# External_boards.net
KiCad netlist of a schematic drawn in Altium Designer
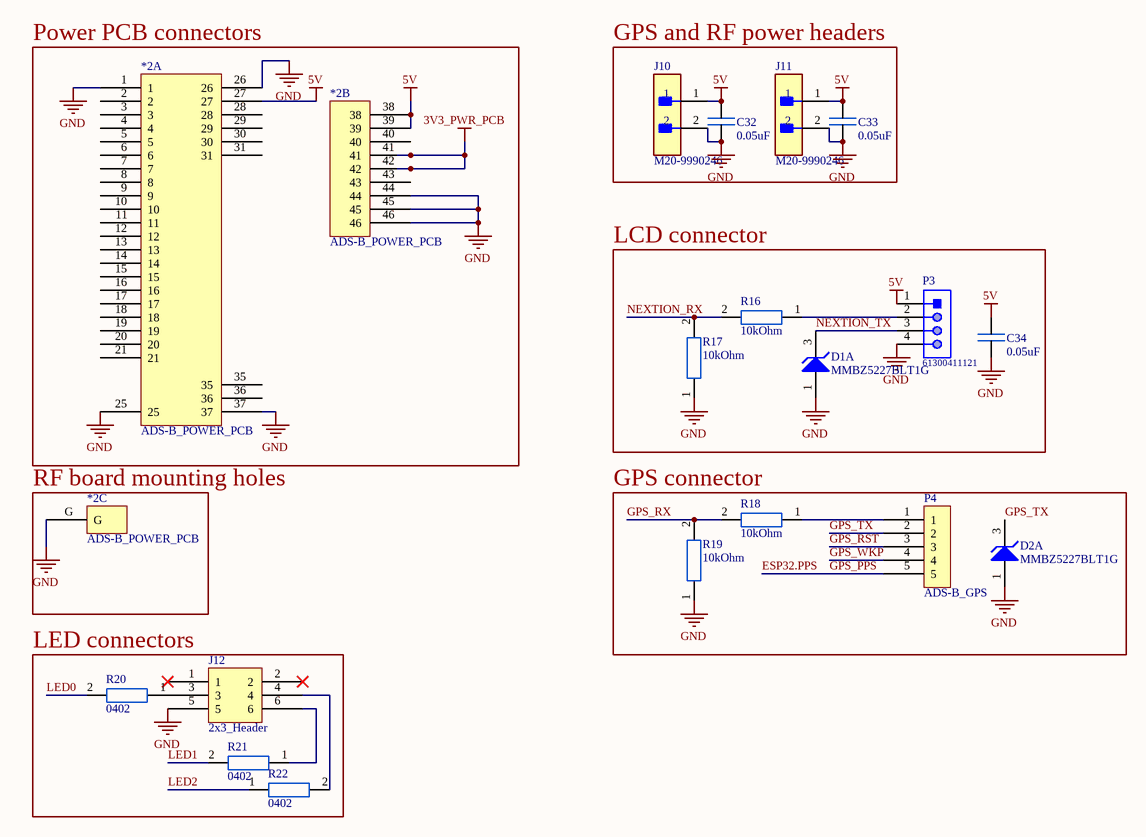
[diagram p0: External_boards.SchDoc]

(export (version "E")
  (design (tool "Eeschema 10.0.6"))
  (components
    (comp (ref "*2")
      (value "ADS-B_POWER_PCB")
      (footprint "ADS-B_POWER_PCB")
      (libsource (lib "Schlib1") (part "ADS-B_POWER_PCB"))
    )
    (comp (ref "C32")
      (value "0.05uF")
      (footprint "0402_footprint")
      (description "0402 capacitor")
      (libsource (lib "Schlib1") (part "Capacitor_0402"))
    )
    (comp (ref "C33")
      (value "0.05uF")
      (footprint "0402_footprint")
      (description "0402 capacitor")
      (libsource (lib "Schlib1") (part "Capacitor_0402"))
    )
    (comp (ref "C34")
      (value "0.05uF")
      (footprint "0402_footprint")
      (description "0402 capacitor")
      (libsource (lib "Schlib1") (part "Capacitor_0402"))
    )
    (comp (ref "D1")
      (value "MMBZ5227BLT1G")
      (footprint "ONSC-SOT-23-3-318-08_V")
      (description "Zener Voltage Regulator, 225 mW, 3-Pin SOT-23, Pb-Free, Tape and Reel")
      (fields (field (name "MANUFACTURER") "On Semiconductor"))
      (libsource (lib "Altium Content Vault") (part "ONSC-A1K3-3"))
    )
    (comp (ref "D2")
      (value "MMBZ5227BLT1G")
      (footprint "ONSC-SOT-23-3-318-08_V")
      (description "Zener Voltage Regulator, 225 mW, 3-Pin SOT-23, Pb-Free, Tape and Reel")
      (fields (field (name "MANUFACTURER") "On Semiconductor"))
      (libsource (lib "Altium Content Vault") (part "ONSC-A1K3-3"))
    )
    (comp (ref "J10")
      (value "M20-9990246")
      (footprint "FP-M20-9990246-MFG")
      (description "CONN HEADER VERT 2POS 2.54MM")
      (fields
        (field (name "OCTOPART") "https://octopart.com/m20-9990246-harwin-2590635")
        (field (name "MANUFACTURER") "Harwin")
      )
      (libsource (lib "Altium Content Vault") (part "3bc925449376181038e59eaffc5286c"))
    )
    (comp (ref "J11")
      (value "M20-9990246")
      (footprint "FP-M20-9990246-MFG")
      (description "CONN HEADER VERT 2POS 2.54MM")
      (fields
        (field (name "OCTOPART") "https://octopart.com/m20-9990246-harwin-2590635")
        (field (name "MANUFACTURER") "Harwin")
      )
      (libsource (lib "Altium Content Vault") (part "3bc925449376181038e59eaffc5286c"))
    )
    (comp (ref "J12")
      (value "2x3_Header")
      (footprint "2x3 header")
      (libsource (lib "Schlib1") (part "2x3_Header"))
    )
    (comp (ref "P3")
      (value "61300411121")
      (footprint "61300411121")
      (description "THT Vertical Pin Header WR-PHD, Pitch 2.54 mm, Single Row, 4 pins")
      (fields (field (name "MANUFACTURER") "Wurth Elektronik") (field (name "PUBLISHER") "WurthElektronik"))
      (libsource (lib "Altium Content Vault") (part "WE-CN-1P-M-R4"))
    )
    (comp (ref "P4")
      (value "ADS-B_GPS")
      (footprint "ADS-B_GPS")
      (libsource (lib "Schlib1") (part "ADS-B_GPS"))
    )
    (comp (ref "R16")
      (value "10kOhm")
      (footprint "0402_footprint")
      (description "0402 resistor")
      (libsource (lib "Schlib1") (part "Resistor_0402"))
    )
    (comp (ref "R17")
      (value "10kOhm")
      (footprint "0402_footprint")
      (description "0402 resistor")
      (libsource (lib "Schlib1") (part "Resistor_0402"))
    )
    (comp (ref "R18")
      (value "10kOhm")
      (footprint "0402_footprint")
      (description "0402 resistor")
      (libsource (lib "Schlib1") (part "Resistor_0402"))
    )
    (comp (ref "R19")
      (value "10kOhm")
      (footprint "0402_footprint")
      (description "0402 resistor")
      (libsource (lib "Schlib1") (part "Resistor_0402"))
    )
    (comp (ref "R20")
      (value "0402")
      (footprint "0402_footprint")
      (description "0402 resistor")
      (libsource (lib "Schlib1") (part "Resistor_0402"))
    )
    (comp (ref "R21")
      (value "0402")
      (footprint "0402_footprint")
      (description "0402 resistor")
      (libsource (lib "Schlib1") (part "Resistor_0402"))
    )
    (comp (ref "R22")
      (value "0402")
      (footprint "0402_footprint")
      (description "0402 resistor")
      (libsource (lib "Schlib1") (part "Resistor_0402"))
    )
  )
  (nets
    (net (code "1") (name "/ESP32.PPS") (class "Default")
      (node (ref "P4") (pin "5") (pinfunction "5_5") (pintype "passive"))
    )
    (net (code "2") (name "/GPS_RST") (class "Default")
      (node (ref "P4") (pin "3") (pinfunction "3_3") (pintype "passive"))
    )
    (net (code "3") (name "/GPS_RX") (class "Default")
      (node (ref "R18") (pin "2") (pinfunction "2_2") (pintype "passive"))
      (node (ref "R19") (pin "2") (pinfunction "2_2") (pintype "passive"))
    )
    (net (code "4") (name "/GPS_TX") (class "Default")
      (node (ref "D2") (pin "3") (pinfunction "K_3") (pintype "passive"))
      (node (ref "P4") (pin "2") (pinfunction "2_2") (pintype "passive"))
    )
    (net (code "5") (name "/GPS_WKP") (class "Default")
      (node (ref "P4") (pin "4") (pinfunction "4_4") (pintype "passive"))
    )
    (net (code "6") (name "/LED0") (class "Default")
      (node (ref "R20") (pin "2") (pinfunction "2_2") (pintype "passive"))
    )
    (net (code "7") (name "/LED1") (class "Default")
      (node (ref "R21") (pin "2") (pinfunction "2_2") (pintype "passive"))
    )
    (net (code "8") (name "/LED2") (class "Default")
      (node (ref "R22") (pin "1") (pinfunction "1_1") (pintype "passive"))
    )
    (net (code "9") (name "/NEXTION_RX") (class "Default")
      (node (ref "R16") (pin "2") (pinfunction "2_2") (pintype "passive"))
      (node (ref "R17") (pin "2") (pinfunction "2_2") (pintype "passive"))
    )
    (net (code "10") (name "/NEXTION_TX") (class "Default")
      (node (ref "D1") (pin "3") (pinfunction "K_3") (pintype "passive"))
      (node (ref "P3") (pin "3") (pinfunction "3_3") (pintype "passive"))
    )
    (net (code "11") (name "3V3_PWR_PCB") (class "Default")
      (node (ref "*2") (pin "41") (pinfunction "41_41") (pintype "passive"))
      (node (ref "*2") (pin "42") (pinfunction "42_42") (pintype "passive"))
    )
    (net (code "12") (name "5V") (class "Default")
      (node (ref "*2") (pin "27") (pinfunction "27_27") (pintype "passive"))
      (node (ref "*2") (pin "38") (pinfunction "38_38") (pintype "passive"))
      (node (ref "*2") (pin "39") (pinfunction "39_39") (pintype "passive"))
      (node (ref "C32") (pin "2") (pinfunction "2_2") (pintype "passive"))
      (node (ref "C33") (pin "2") (pinfunction "2_2") (pintype "passive"))
      (node (ref "C34") (pin "2") (pinfunction "2_2") (pintype "passive"))
      (node (ref "J10") (pin "1") (pinfunction "1_1") (pintype "passive"))
      (node (ref "J11") (pin "1") (pinfunction "1_1") (pintype "passive"))
      (node (ref "P3") (pin "1") (pinfunction "1_1") (pintype "passive"))
    )
    (net (code "13") (name "GND") (class "Default")
      (node (ref "*2") (pin "1") (pinfunction "1_1") (pintype "passive"))
      (node (ref "*2") (pin "25") (pinfunction "25_25") (pintype "passive"))
      (node (ref "*2") (pin "26") (pinfunction "26_26") (pintype "passive"))
      (node (ref "*2") (pin "37") (pinfunction "37_37") (pintype "passive"))
      (node (ref "*2") (pin "44") (pinfunction "44_44") (pintype "passive"))
      (node (ref "*2") (pin "45") (pinfunction "45_45") (pintype "passive"))
      (node (ref "*2") (pin "46") (pinfunction "46_46") (pintype "passive"))
      (node (ref "*2") (pin "G") (pinfunction "G_G") (pintype "passive"))
      (node (ref "C32") (pin "1") (pinfunction "1_1") (pintype "passive"))
      (node (ref "C33") (pin "1") (pinfunction "1_1") (pintype "passive"))
      (node (ref "C34") (pin "1") (pinfunction "1_1") (pintype "passive"))
      (node (ref "D1") (pin "1") (pinfunction "A_1") (pintype "passive"))
      (node (ref "D2") (pin "1") (pinfunction "A_1") (pintype "passive"))
      (node (ref "J10") (pin "2") (pinfunction "2_2") (pintype "passive"))
      (node (ref "J11") (pin "2") (pinfunction "2_2") (pintype "passive"))
      (node (ref "J12") (pin "5") (pinfunction "5_5") (pintype "passive"))
      (node (ref "P3") (pin "4") (pinfunction "4_4") (pintype "passive"))
      (node (ref "R17") (pin "1") (pinfunction "1_1") (pintype "passive"))
      (node (ref "R19") (pin "1") (pinfunction "1_1") (pintype "passive"))
    )
    (net (code "14") (name "Net-(J12-Pad3)") (class "Default")
      (node (ref "J12") (pin "3") (pinfunction "3_3") (pintype "passive"))
      (node (ref "R20") (pin "1") (pinfunction "1_1") (pintype "passive"))
    )
    (net (code "15") (name "Net-(J12-Pad4)") (class "Default")
      (node (ref "J12") (pin "4") (pinfunction "4_4") (pintype "passive"))
      (node (ref "R22") (pin "2") (pinfunction "2_2") (pintype "passive"))
    )
    (net (code "16") (name "Net-(J12-Pad6)") (class "Default")
      (node (ref "J12") (pin "6") (pinfunction "6_6") (pintype "passive"))
      (node (ref "R21") (pin "1") (pinfunction "1_1") (pintype "passive"))
    )
    (net (code "17") (name "Net-(P3-Pad2)") (class "Default")
      (node (ref "P3") (pin "2") (pinfunction "2_2") (pintype "passive"))
      (node (ref "R16") (pin "1") (pinfunction "1_1") (pintype "passive"))
    )
    (net (code "18") (name "Net-(P4-Pad1)") (class "Default")
      (node (ref "P4") (pin "1") (pinfunction "1_1") (pintype "passive"))
      (node (ref "R18") (pin "1") (pinfunction "1_1") (pintype "passive"))
    )
    (net (code "19") (name "unconnected-(*2-Pad2)") (class "Default")
      (node (ref "*2") (pin "2") (pinfunction "2_2") (pintype "passive"))
    )
    (net (code "20") (name "unconnected-(*2-Pad3)") (class "Default")
      (node (ref "*2") (pin "3") (pinfunction "3_3") (pintype "passive"))
    )
    (net (code "21") (name "unconnected-(*2-Pad4)") (class "Default")
      (node (ref "*2") (pin "4") (pinfunction "4_4") (pintype "passive"))
    )
    (net (code "22") (name "unconnected-(*2-Pad5)") (class "Default")
      (node (ref "*2") (pin "5") (pinfunction "5_5") (pintype "passive"))
    )
    (net (code "23") (name "unconnected-(*2-Pad6)") (class "Default")
      (node (ref "*2") (pin "6") (pinfunction "6_6") (pintype "passive"))
    )
    (net (code "24") (name "unconnected-(*2-Pad7)") (class "Default")
      (node (ref "*2") (pin "7") (pinfunction "7_7") (pintype "passive"))
    )
    (net (code "25") (name "unconnected-(*2-Pad8)") (class "Default")
      (node (ref "*2") (pin "8") (pinfunction "8_8") (pintype "passive"))
    )
    (net (code "26") (name "unconnected-(*2-Pad9)") (class "Default")
      (node (ref "*2") (pin "9") (pinfunction "9_9") (pintype "passive"))
    )
    (net (code "27") (name "unconnected-(*2-Pad10)") (class "Default")
      (node (ref "*2") (pin "10") (pinfunction "10_10") (pintype "passive"))
    )
    (net (code "28") (name "unconnected-(*2-Pad11)") (class "Default")
      (node (ref "*2") (pin "11") (pinfunction "11_11") (pintype "passive"))
    )
    (net (code "29") (name "unconnected-(*2-Pad12)") (class "Default")
      (node (ref "*2") (pin "12") (pinfunction "12_12") (pintype "passive"))
    )
    (net (code "30") (name "unconnected-(*2-Pad13)") (class "Default")
      (node (ref "*2") (pin "13") (pinfunction "13_13") (pintype "passive"))
    )
    (net (code "31") (name "unconnected-(*2-Pad14)") (class "Default")
      (node (ref "*2") (pin "14") (pinfunction "14_14") (pintype "passive"))
    )
    (net (code "32") (name "unconnected-(*2-Pad15)") (class "Default")
      (node (ref "*2") (pin "15") (pinfunction "15_15") (pintype "passive"))
    )
    (net (code "33") (name "unconnected-(*2-Pad16)") (class "Default")
      (node (ref "*2") (pin "16") (pinfunction "16_16") (pintype "passive"))
    )
    (net (code "34") (name "unconnected-(*2-Pad17)") (class "Default")
      (node (ref "*2") (pin "17") (pinfunction "17_17") (pintype "passive"))
    )
    (net (code "35") (name "unconnected-(*2-Pad18)") (class "Default")
      (node (ref "*2") (pin "18") (pinfunction "18_18") (pintype "passive"))
    )
    (net (code "36") (name "unconnected-(*2-Pad19)") (class "Default")
      (node (ref "*2") (pin "19") (pinfunction "19_19") (pintype "passive"))
    )
    (net (code "37") (name "unconnected-(*2-Pad20)") (class "Default")
      (node (ref "*2") (pin "20") (pinfunction "20_20") (pintype "passive"))
    )
    (net (code "38") (name "unconnected-(*2-Pad21)") (class "Default")
      (node (ref "*2") (pin "21") (pinfunction "21_21") (pintype "passive"))
    )
    (net (code "39") (name "unconnected-(*2-Pad28)") (class "Default")
      (node (ref "*2") (pin "28") (pinfunction "28_28") (pintype "passive"))
    )
    (net (code "40") (name "unconnected-(*2-Pad29)") (class "Default")
      (node (ref "*2") (pin "29") (pinfunction "29_29") (pintype "passive"))
    )
    (net (code "41") (name "unconnected-(*2-Pad30)") (class "Default")
      (node (ref "*2") (pin "30") (pinfunction "30_30") (pintype "passive"))
    )
    (net (code "42") (name "unconnected-(*2-Pad31)") (class "Default")
      (node (ref "*2") (pin "31") (pinfunction "31_31") (pintype "passive"))
    )
    (net (code "43") (name "unconnected-(*2-Pad35)") (class "Default")
      (node (ref "*2") (pin "35") (pinfunction "35_35") (pintype "passive"))
    )
    (net (code "44") (name "unconnected-(*2-Pad36)") (class "Default")
      (node (ref "*2") (pin "36") (pinfunction "36_36") (pintype "passive"))
    )
    (net (code "45") (name "unconnected-(*2-Pad40)") (class "Default")
      (node (ref "*2") (pin "40") (pinfunction "40_40") (pintype "passive"))
    )
    (net (code "46") (name "unconnected-(*2-Pad43)") (class "Default")
      (node (ref "*2") (pin "43") (pinfunction "43_43") (pintype "passive"))
    )
    (net (code "47") (name "unconnected-(J12-Pad1)") (class "Default")
      (node (ref "J12") (pin "1") (pinfunction "1_1") (pintype "passive+no_connect"))
    )
    (net (code "48") (name "unconnected-(J12-Pad2)") (class "Default")
      (node (ref "J12") (pin "2") (pinfunction "2_2") (pintype "passive+no_connect"))
    )
  )
)
